# looter_round_molocs.net
KiCad netlist of a schematic drawn in EAGLE
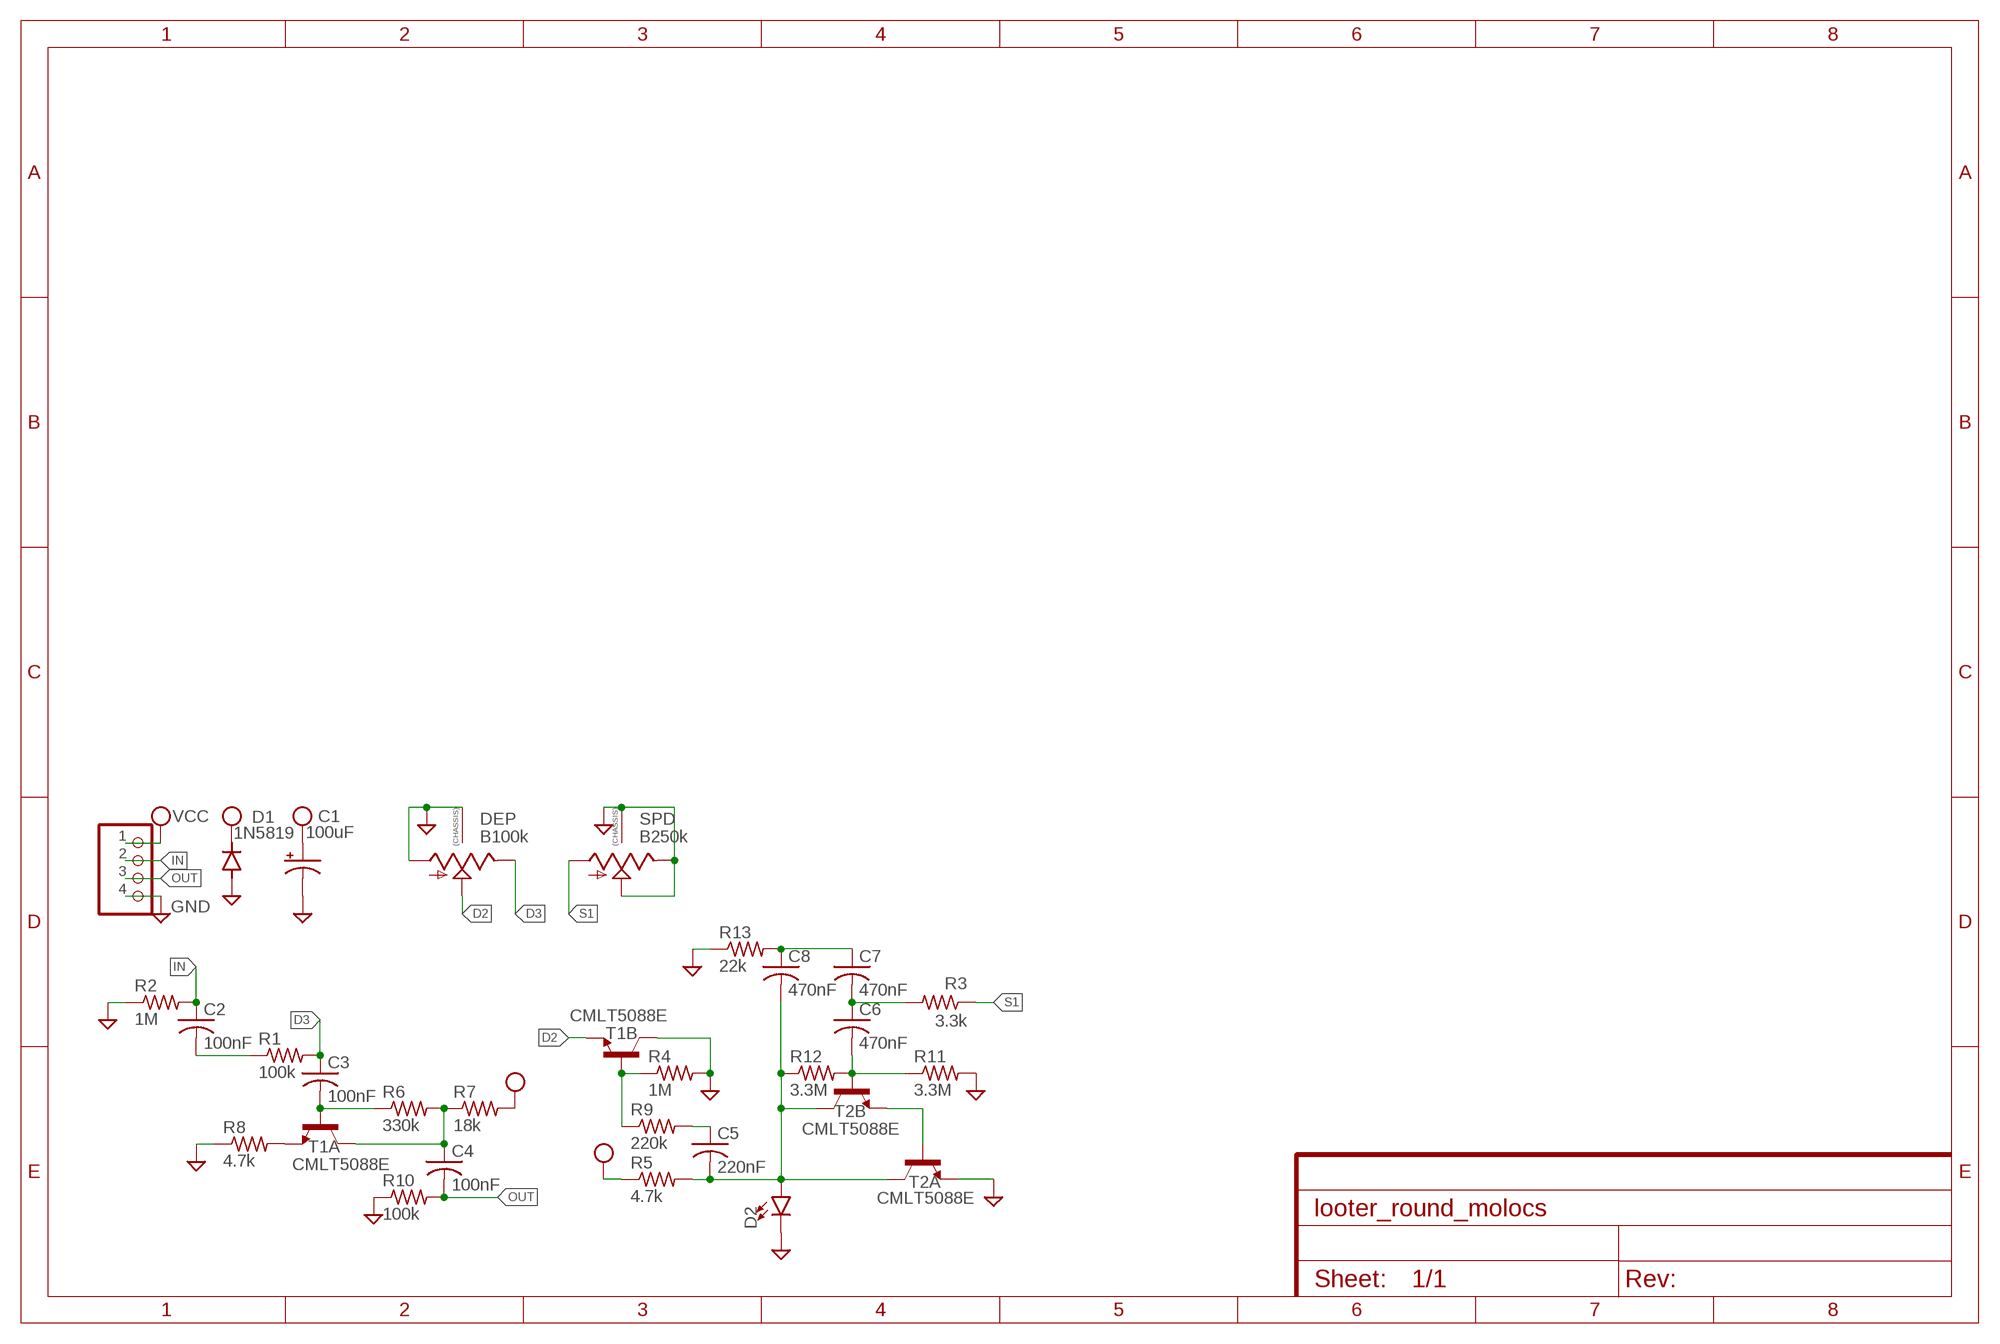
[diagram p0: schematic, sheet 1]

(export (version "E")
  (design (tool "Eeschema 10.0.6"))
  (components
    (comp (ref "C1")
      (value "100uF")
      (footprint "eagle-import:PAN_B_SMD+THRU")
      (libsource (lib "eagle-import") (part "CAP_SMD+THRUPAN_B"))
    )
    (comp (ref "C2")
      (value "100nF")
      (footprint "eagle-import:C0603")
      (libsource (lib "eagle-import") (part "C-USC0603"))
    )
    (comp (ref "C3")
      (value "100nF")
      (footprint "eagle-import:C0603")
      (libsource (lib "eagle-import") (part "C-USC0603"))
    )
    (comp (ref "C4")
      (value "100nF")
      (footprint "eagle-import:C0603")
      (libsource (lib "eagle-import") (part "C-USC0603"))
    )
    (comp (ref "C5")
      (value "220nF")
      (footprint "eagle-import:C0603")
      (libsource (lib "eagle-import") (part "C-USC0603"))
    )
    (comp (ref "C6")
      (value "470nF")
      (footprint "eagle-import:C0603")
      (libsource (lib "eagle-import") (part "C-USC0603"))
    )
    (comp (ref "C7")
      (value "470nF")
      (footprint "eagle-import:C0603")
      (libsource (lib "eagle-import") (part "C-USC0603"))
    )
    (comp (ref "C8")
      (value "470nF")
      (footprint "eagle-import:C0603")
      (libsource (lib "eagle-import") (part "C-USC0603"))
    )
    (comp (ref "D1")
      (value "1N5819")
      (footprint "eagle-import:SOD123")
      (libsource (lib "eagle-import") (part "DIODE-SOD123"))
    )
    (comp (ref "D2")
      (value "LED0603")
      (footprint "eagle-import:LED-0603")
      (libsource (lib "eagle-import") (part "LED0603"))
    )
    (comp (ref "DEP")
      (value "B100k")
      (footprint "eagle-import:9MM_SNAP-IN_POT")
      (libsource (lib "eagle-import") (part "9MM_SNAP-IN_POT_CHASSIS"))
    )
    (comp (ref "JP1")
      (value "PINHD-1X4")
      (footprint "eagle-import:1X04")
      (libsource (lib "eagle-import") (part "PINHD-1X4"))
    )
    (comp (ref "R1")
      (value "100k")
      (footprint "eagle-import:R0603")
      (libsource (lib "eagle-import") (part "R-US_R0603"))
    )
    (comp (ref "R2")
      (value "1M")
      (footprint "eagle-import:R0603")
      (libsource (lib "eagle-import") (part "R-US_R0603"))
    )
    (comp (ref "R3")
      (value "3.3k")
      (footprint "eagle-import:R0603")
      (libsource (lib "eagle-import") (part "R-US_R0603"))
    )
    (comp (ref "R4")
      (value "1M")
      (footprint "eagle-import:R0603")
      (libsource (lib "eagle-import") (part "R-US_R0603"))
    )
    (comp (ref "R5")
      (value "4.7k")
      (footprint "eagle-import:R0603")
      (libsource (lib "eagle-import") (part "R-US_R0603"))
    )
    (comp (ref "R6")
      (value "330k")
      (footprint "eagle-import:R0603")
      (libsource (lib "eagle-import") (part "R-US_R0603"))
    )
    (comp (ref "R7")
      (value "18k")
      (footprint "eagle-import:R0603")
      (libsource (lib "eagle-import") (part "R-US_R0603"))
    )
    (comp (ref "R8")
      (value "4.7k")
      (footprint "eagle-import:R0603")
      (libsource (lib "eagle-import") (part "R-US_R0603"))
    )
    (comp (ref "R9")
      (value "220k")
      (footprint "eagle-import:R0603")
      (libsource (lib "eagle-import") (part "R-US_R0603"))
    )
    (comp (ref "R10")
      (value "100k")
      (footprint "eagle-import:R0603")
      (libsource (lib "eagle-import") (part "R-US_R0603"))
    )
    (comp (ref "R11")
      (value "3.3M")
      (footprint "eagle-import:R0603")
      (libsource (lib "eagle-import") (part "R-US_R0603"))
    )
    (comp (ref "R12")
      (value "3.3M")
      (footprint "eagle-import:R0603")
      (libsource (lib "eagle-import") (part "R-US_R0603"))
    )
    (comp (ref "R13")
      (value "22k")
      (footprint "eagle-import:R0603")
      (libsource (lib "eagle-import") (part "R-US_R0603"))
    )
    (comp (ref "SPD")
      (value "B250k")
      (footprint "eagle-import:9MM_SNAP-IN_POT")
      (libsource (lib "eagle-import") (part "9MM_SNAP-IN_POT_CHASSIS"))
    )
    (comp (ref "T1")
      (value "CMLT5088E")
      (footprint "eagle-import:SOT563")
      (libsource (lib "eagle-import") (part "CMLT5088E"))
    )
    (comp (ref "T2")
      (value "CMLT5088E")
      (footprint "eagle-import:SOT563")
      (libsource (lib "eagle-import") (part "CMLT5088E"))
    )
  )
  (nets
    (net (code "1") (name "D2") (class "Default")
      (node (ref "DEP") (pin "2") (pinfunction "S_2") (pintype "passive"))
      (node (ref "T1") (pin "4") (pinfunction "E_4") (pintype "passive"))
    )
    (net (code "2") (name "D3") (class "Default")
      (node (ref "C3") (pin "1") (pinfunction "1_1") (pintype "passive"))
      (node (ref "DEP") (pin "3") (pinfunction "E_3") (pintype "passive"))
      (node (ref "R1") (pin "2") (pinfunction "2_2") (pintype "passive"))
    )
    (net (code "3") (name "GND") (class "Default")
      (node (ref "C1") (pin "-") (pinfunction "-_-") (pintype "passive"))
      (node (ref "C1") (pin "--") (pinfunction "-_--") (pintype "passive"))
      (node (ref "D1") (pin "A") (pinfunction "A_A") (pintype "passive"))
      (node (ref "D2") (pin "C") (pinfunction "C_C") (pintype "passive"))
      (node (ref "DEP") (pin "1") (pinfunction "A_1") (pintype "passive"))
      (node (ref "DEP") (pin "CHASSIS1") (pinfunction "P$1_CHASSIS1") (pintype "passive"))
      (node (ref "DEP") (pin "CHASSIS2") (pinfunction "P$1_CHASSIS2") (pintype "passive"))
      (node (ref "JP1") (pin "4") (pinfunction "4_4") (pintype "passive"))
      (node (ref "R10") (pin "1") (pinfunction "1_1") (pintype "passive"))
      (node (ref "R11") (pin "2") (pinfunction "2_2") (pintype "passive"))
      (node (ref "R13") (pin "1") (pinfunction "1_1") (pintype "passive"))
      (node (ref "R2") (pin "1") (pinfunction "1_1") (pintype "passive"))
      (node (ref "R4") (pin "2") (pinfunction "2_2") (pintype "passive"))
      (node (ref "R8") (pin "1") (pinfunction "1_1") (pintype "passive"))
      (node (ref "SPD") (pin "2") (pinfunction "S_2") (pintype "passive"))
      (node (ref "SPD") (pin "3") (pinfunction "E_3") (pintype "passive"))
      (node (ref "SPD") (pin "CHASSIS1") (pinfunction "P$1_CHASSIS1") (pintype "passive"))
      (node (ref "SPD") (pin "CHASSIS2") (pinfunction "P$1_CHASSIS2") (pintype "passive"))
      (node (ref "T1") (pin "3") (pinfunction "C_3") (pintype "passive"))
      (node (ref "T2") (pin "1") (pinfunction "E_1") (pintype "passive"))
    )
    (net (code "4") (name "IN") (class "Default")
      (node (ref "C2") (pin "1") (pinfunction "1_1") (pintype "passive"))
      (node (ref "JP1") (pin "2") (pinfunction "2_2") (pintype "passive"))
      (node (ref "R2") (pin "2") (pinfunction "2_2") (pintype "passive"))
    )
    (net (code "5") (name "Net-(C2-Pad2)") (class "Default")
      (node (ref "C2") (pin "2") (pinfunction "2_2") (pintype "passive"))
      (node (ref "R1") (pin "1") (pinfunction "1_1") (pintype "passive"))
    )
    (net (code "6") (name "Net-(C5-Pad1)") (class "Default")
      (node (ref "C5") (pin "1") (pinfunction "1_1") (pintype "passive"))
      (node (ref "R9") (pin "2") (pinfunction "2_2") (pintype "passive"))
    )
    (net (code "7") (name "Net-(C6-Pad1)") (class "Default")
      (node (ref "C6") (pin "1") (pinfunction "1_1") (pintype "passive"))
      (node (ref "C7") (pin "2") (pinfunction "2_2") (pintype "passive"))
      (node (ref "R3") (pin "2") (pinfunction "2_2") (pintype "passive"))
    )
    (net (code "8") (name "Net-(C7-Pad1)") (class "Default")
      (node (ref "C7") (pin "1") (pinfunction "1_1") (pintype "passive"))
      (node (ref "C8") (pin "1") (pinfunction "1_1") (pintype "passive"))
      (node (ref "R13") (pin "2") (pinfunction "2_2") (pintype "passive"))
    )
    (net (code "9") (name "Net-(T1A-B)") (class "Default")
      (node (ref "C3") (pin "2") (pinfunction "2_2") (pintype "passive"))
      (node (ref "R6") (pin "1") (pinfunction "1_1") (pintype "passive"))
      (node (ref "T1") (pin "2") (pinfunction "B_2") (pintype "passive"))
    )
    (net (code "10") (name "Net-(T1A-C)") (class "Default")
      (node (ref "C4") (pin "1") (pinfunction "1_1") (pintype "passive"))
      (node (ref "R6") (pin "2") (pinfunction "2_2") (pintype "passive"))
      (node (ref "R7") (pin "1") (pinfunction "1_1") (pintype "passive"))
      (node (ref "T1") (pin "6") (pinfunction "C_6") (pintype "passive"))
    )
    (net (code "11") (name "Net-(T1A-E)") (class "Default")
      (node (ref "R8") (pin "2") (pinfunction "2_2") (pintype "passive"))
      (node (ref "T1") (pin "1") (pinfunction "E_1") (pintype "passive"))
    )
    (net (code "12") (name "Net-(T1B-B)") (class "Default")
      (node (ref "R4") (pin "1") (pinfunction "1_1") (pintype "passive"))
      (node (ref "R9") (pin "1") (pinfunction "1_1") (pintype "passive"))
      (node (ref "T1") (pin "5") (pinfunction "B_5") (pintype "passive"))
    )
    (net (code "13") (name "Net-(T2A-B)") (class "Default")
      (node (ref "T2") (pin "2") (pinfunction "B_2") (pintype "passive"))
      (node (ref "T2") (pin "4") (pinfunction "E_4") (pintype "passive"))
    )
    (net (code "14") (name "Net-(T2A-C)") (class "Default")
      (node (ref "C5") (pin "2") (pinfunction "2_2") (pintype "passive"))
      (node (ref "C8") (pin "2") (pinfunction "2_2") (pintype "passive"))
      (node (ref "D2") (pin "A") (pinfunction "A_A") (pintype "passive"))
      (node (ref "R12") (pin "1") (pinfunction "1_1") (pintype "passive"))
      (node (ref "R5") (pin "2") (pinfunction "2_2") (pintype "passive"))
      (node (ref "T2") (pin "3") (pinfunction "C_3") (pintype "passive"))
      (node (ref "T2") (pin "6") (pinfunction "C_6") (pintype "passive"))
    )
    (net (code "15") (name "Net-(T2B-B)") (class "Default")
      (node (ref "C6") (pin "2") (pinfunction "2_2") (pintype "passive"))
      (node (ref "R11") (pin "1") (pinfunction "1_1") (pintype "passive"))
      (node (ref "R12") (pin "2") (pinfunction "2_2") (pintype "passive"))
      (node (ref "T2") (pin "5") (pinfunction "B_5") (pintype "passive"))
    )
    (net (code "16") (name "OUT") (class "Default")
      (node (ref "C4") (pin "2") (pinfunction "2_2") (pintype "passive"))
      (node (ref "JP1") (pin "3") (pinfunction "3_3") (pintype "passive"))
      (node (ref "R10") (pin "2") (pinfunction "2_2") (pintype "passive"))
    )
    (net (code "17") (name "S1") (class "Default")
      (node (ref "R3") (pin "1") (pinfunction "1_1") (pintype "passive"))
      (node (ref "SPD") (pin "1") (pinfunction "A_1") (pintype "passive"))
    )
    (net (code "18") (name "VCC") (class "Default")
      (node (ref "C1") (pin "+") (pinfunction "+_+") (pintype "passive"))
      (node (ref "C1") (pin "++") (pinfunction "+_++") (pintype "passive"))
      (node (ref "D1") (pin "C") (pinfunction "C_C") (pintype "passive"))
      (node (ref "JP1") (pin "1") (pinfunction "1_1") (pintype "passive"))
      (node (ref "R5") (pin "1") (pinfunction "1_1") (pintype "passive"))
      (node (ref "R7") (pin "2") (pinfunction "2_2") (pintype "passive"))
    )
  )
)
